# me433_hw2.net
KiCad netlist of a schematic drawn in EAGLE
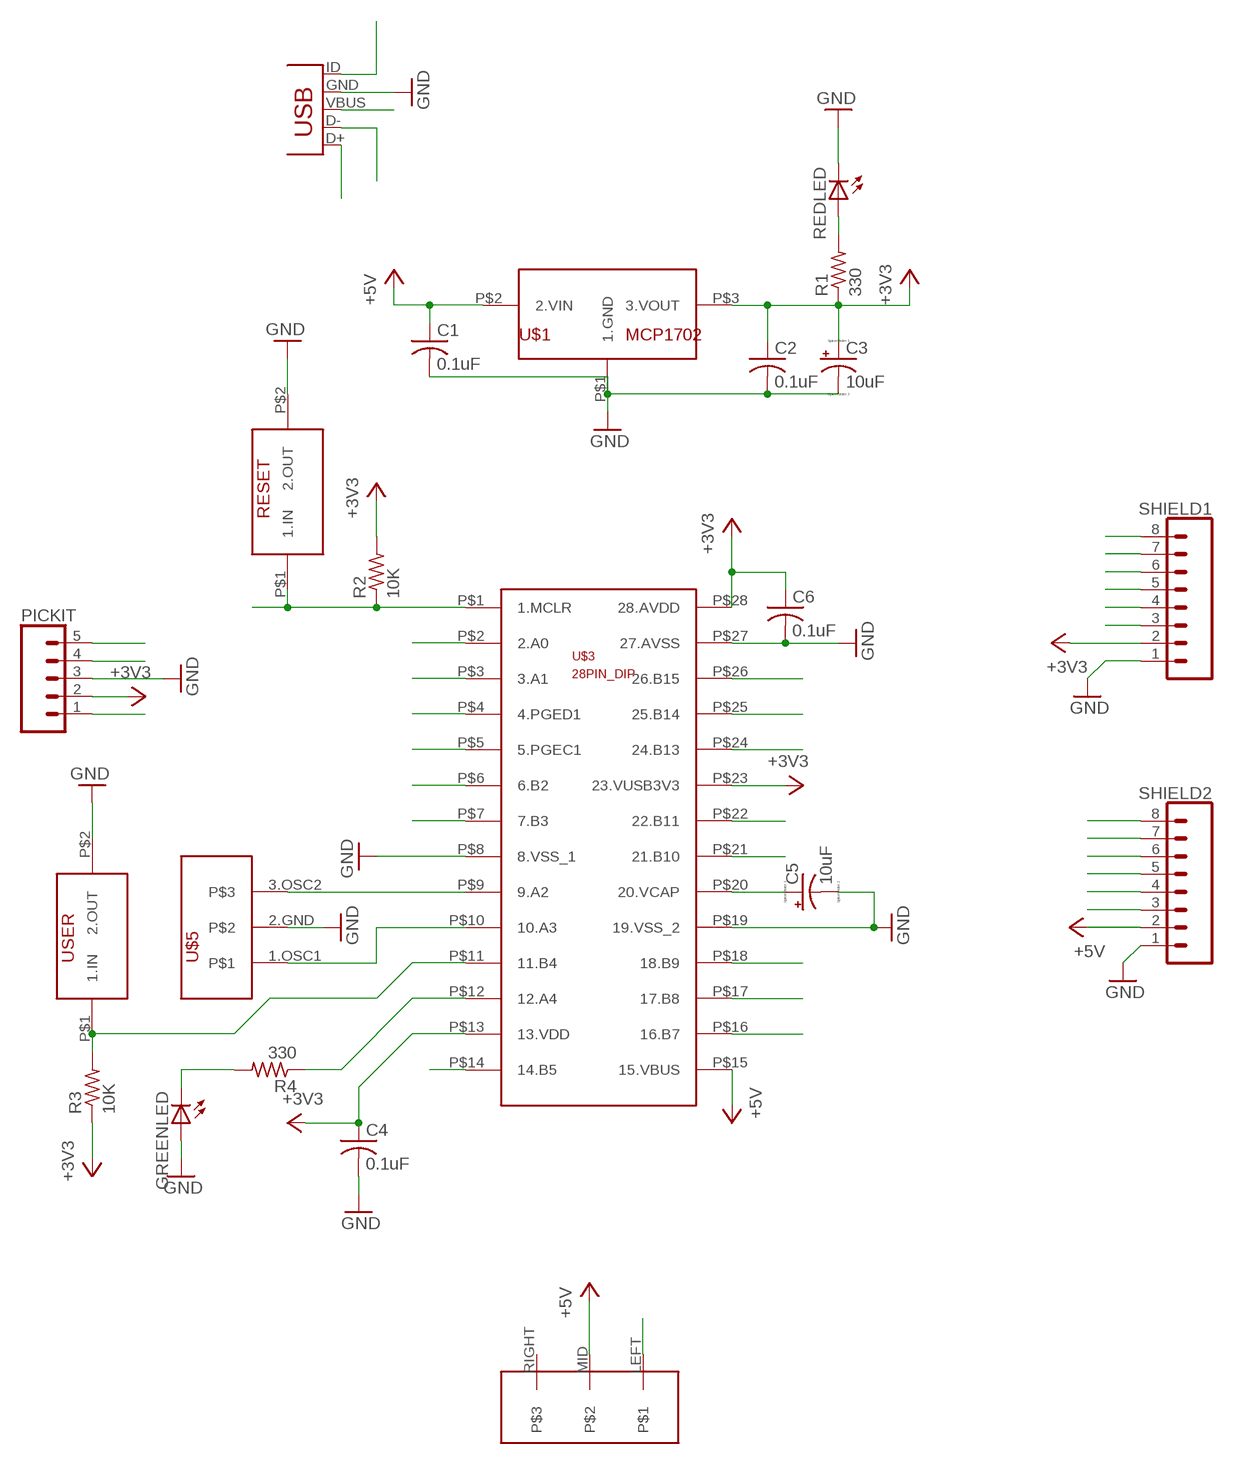
[diagram p0: schematic, sheet 1]

(export (version "E")
  (design (tool "Eeschema 10.0.6"))
  (components
    (comp (ref "C1")
      (value "0.1uF")
      (footprint "eagle-import:C025-030X050")
      (libsource (lib "eagle-import") (part "C-US025-030X050"))
    )
    (comp (ref "C2")
      (value "0.1uF")
      (footprint "eagle-import:C025-030X050")
      (libsource (lib "eagle-import") (part "C-US025-030X050"))
    )
    (comp (ref "C3")
      (value "10uF")
      (footprint "eagle-import:B45181B")
      (libsource (lib "eagle-import") (part "CPOL-USB45181B"))
    )
    (comp (ref "C4")
      (value "0.1uF")
      (footprint "eagle-import:C025-030X050")
      (libsource (lib "eagle-import") (part "C-US025-030X050"))
    )
    (comp (ref "C5")
      (value "10uF")
      (footprint "eagle-import:B45181B")
      (libsource (lib "eagle-import") (part "CPOL-USB45181B"))
    )
    (comp (ref "C6")
      (value "0.1uF")
      (footprint "eagle-import:C025-030X050")
      (libsource (lib "eagle-import") (part "C-US025-030X050"))
    )
    (comp (ref "GREENLED")
      (value "LED3MM")
      (footprint "eagle-import:LED3MM")
      (libsource (lib "eagle-import") (part "LED3MM"))
    )
    (comp (ref "PICKIT")
      (value "CONN_05")
      (footprint "eagle-import:1X05")
      (libsource (lib "eagle-import") (part "CONN_05"))
    )
    (comp (ref "R1")
      (value "330")
      (footprint "eagle-import:0207_10")
      (libsource (lib "eagle-import") (part "R-US_0207/10"))
    )
    (comp (ref "R2")
      (value "10K")
      (footprint "eagle-import:0207_10")
      (libsource (lib "eagle-import") (part "R-US_0207/10"))
    )
    (comp (ref "R3")
      (value "10K")
      (footprint "eagle-import:0207_10")
      (libsource (lib "eagle-import") (part "R-US_0207/10"))
    )
    (comp (ref "R4")
      (value "330")
      (footprint "eagle-import:0207_10")
      (libsource (lib "eagle-import") (part "R-US_0207/10"))
    )
    (comp (ref "REDLED")
      (value "LED3MM")
      (footprint "eagle-import:LED3MM")
      (libsource (lib "eagle-import") (part "LED3MM"))
    )
    (comp (ref "RESET")
      (value "PUSH_BUTTON")
      (footprint "eagle-import:PUSH_BUTTON")
      (libsource (lib "eagle-import") (part "PUSH_BUTTON"))
    )
    (comp (ref "SHIELD1")
      (value "CONN_08\"")
      (footprint "eagle-import:1X08")
      (libsource (lib "eagle-import") (part "CONN_08{dblquote}"))
    )
    (comp (ref "SHIELD2")
      (value "CONN_08\"")
      (footprint "eagle-import:1X08")
      (libsource (lib "eagle-import") (part "CONN_08{dblquote}"))
    )
    (comp (ref "U$1")
      (value "MCP1702")
      (footprint "eagle-import:MCP1702")
      (libsource (lib "eagle-import") (part "MCP1702"))
    )
    (comp (ref "U$2")
      (value "USBMINIB")
      (footprint "eagle-import:USB-MB-H")
      (libsource (lib "eagle-import") (part "USBMINIB"))
    )
    (comp (ref "U$3")
      (value "28PIN_DIP")
      (footprint "eagle-import:28PIN_DIP")
      (libsource (lib "eagle-import") (part "28PIN_DIP"))
    )
    (comp (ref "U$4")
      (value "SLIDE_SWITCH")
      (footprint "eagle-import:SLIDE_SWITCH")
      (libsource (lib "eagle-import") (part "SLIDE_SWITCH"))
    )
    (comp (ref "U$5")
      (value "RESONATOR")
      (footprint "eagle-import:RESONATOR")
      (libsource (lib "eagle-import") (part "RESONATOR"))
    )
    (comp (ref "USER")
      (value "PUSH_BUTTON")
      (footprint "eagle-import:PUSH_BUTTON")
      (libsource (lib "eagle-import") (part "PUSH_BUTTON"))
    )
  )
  (nets
    (net (code "1") (name "+3V3") (class "Default")
      (node (ref "C2") (pin "1") (pinfunction "1_1") (pintype "passive"))
      (node (ref "C3") (pin "+") (pinfunction "+_+") (pintype "passive"))
      (node (ref "C4") (pin "1") (pinfunction "1_1") (pintype "passive"))
      (node (ref "C6") (pin "1") (pinfunction "1_1") (pintype "passive"))
      (node (ref "PICKIT") (pin "2") (pinfunction "2_2") (pintype "passive"))
      (node (ref "R1") (pin "1") (pinfunction "1_1") (pintype "passive"))
      (node (ref "R2") (pin "2") (pinfunction "2_2") (pintype "passive"))
      (node (ref "R3") (pin "1") (pinfunction "1_1") (pintype "passive"))
      (node (ref "SHIELD1") (pin "2") (pinfunction "2_2") (pintype "passive"))
      (node (ref "U$1") (pin "P$3") (pinfunction "3.VOUT_P$3") (pintype "bidirectional"))
      (node (ref "U$3") (pin "P$13") (pinfunction "13.VDD_P$13") (pintype "bidirectional"))
      (node (ref "U$3") (pin "P$23") (pinfunction "23.VUSB3V3_P$23") (pintype "bidirectional"))
      (node (ref "U$3") (pin "P$28") (pinfunction "28.AVDD_P$28") (pintype "bidirectional"))
    )
    (net (code "2") (name "+5V") (class "Default")
      (node (ref "C1") (pin "1") (pinfunction "1_1") (pintype "passive"))
      (node (ref "SHIELD2") (pin "2") (pinfunction "2_2") (pintype "passive"))
      (node (ref "U$1") (pin "P$2") (pinfunction "2.VIN_P$2") (pintype "bidirectional"))
      (node (ref "U$3") (pin "P$15") (pinfunction "15.VBUS_P$15") (pintype "bidirectional"))
      (node (ref "U$4") (pin "MID") (pinfunction "P$2_MID") (pintype "bidirectional"))
    )
    (net (code "3") (name "/A0") (class "Default")
      (node (ref "SHIELD1") (pin "8") (pinfunction "8_8") (pintype "passive"))
      (node (ref "U$3") (pin "P$2") (pinfunction "2.A0_P$2") (pintype "bidirectional"))
    )
    (net (code "4") (name "/A1") (class "Default")
      (node (ref "SHIELD1") (pin "7") (pinfunction "7_7") (pintype "passive"))
      (node (ref "U$3") (pin "P$3") (pinfunction "3.A1_P$3") (pintype "bidirectional"))
    )
    (net (code "5") (name "/A4") (class "Default")
      (node (ref "R4") (pin "1") (pinfunction "1_1") (pintype "passive"))
      (node (ref "SHIELD1") (pin "3") (pinfunction "3_3") (pintype "passive"))
      (node (ref "U$3") (pin "P$12") (pinfunction "12.A4_P$12") (pintype "bidirectional"))
    )
    (net (code "6") (name "/B2") (class "Default")
      (node (ref "SHIELD1") (pin "6") (pinfunction "6_6") (pintype "passive"))
      (node (ref "U$3") (pin "P$6") (pinfunction "6.B2_P$6") (pintype "bidirectional"))
    )
    (net (code "7") (name "/B3") (class "Default")
      (node (ref "SHIELD1") (pin "5") (pinfunction "5_5") (pintype "passive"))
      (node (ref "U$3") (pin "P$7") (pinfunction "7.B3_P$7") (pintype "bidirectional"))
    )
    (net (code "8") (name "/B4") (class "Default")
      (node (ref "R3") (pin "2") (pinfunction "2_2") (pintype "passive"))
      (node (ref "SHIELD1") (pin "4") (pinfunction "4_4") (pintype "passive"))
      (node (ref "U$3") (pin "P$11") (pinfunction "11.B4_P$11") (pintype "bidirectional"))
      (node (ref "USER") (pin "P$1") (pinfunction "1.IN_P$1") (pintype "bidirectional"))
    )
    (net (code "9") (name "/B7") (class "Default")
      (node (ref "SHIELD2") (pin "3") (pinfunction "3_3") (pintype "passive"))
      (node (ref "U$3") (pin "P$16") (pinfunction "16.B7_P$16") (pintype "bidirectional"))
    )
    (net (code "10") (name "/B8") (class "Default")
      (node (ref "SHIELD2") (pin "4") (pinfunction "4_4") (pintype "passive"))
      (node (ref "U$3") (pin "P$17") (pinfunction "17.B8_P$17") (pintype "bidirectional"))
    )
    (net (code "11") (name "/B9") (class "Default")
      (node (ref "SHIELD2") (pin "5") (pinfunction "5_5") (pintype "passive"))
      (node (ref "U$3") (pin "P$18") (pinfunction "18.B9_P$18") (pintype "bidirectional"))
    )
    (net (code "12") (name "/B13") (class "Default")
      (node (ref "SHIELD2") (pin "6") (pinfunction "6_6") (pintype "passive"))
      (node (ref "U$3") (pin "P$24") (pinfunction "24.B13_P$24") (pintype "bidirectional"))
    )
    (net (code "13") (name "/B14") (class "Default")
      (node (ref "SHIELD2") (pin "7") (pinfunction "7_7") (pintype "passive"))
      (node (ref "U$3") (pin "P$25") (pinfunction "25.B14_P$25") (pintype "bidirectional"))
    )
    (net (code "14") (name "/B15") (class "Default")
      (node (ref "SHIELD2") (pin "8") (pinfunction "8_8") (pintype "passive"))
      (node (ref "U$3") (pin "P$26") (pinfunction "26.B15_P$26") (pintype "bidirectional"))
    )
    (net (code "15") (name "/D+") (class "Default")
      (node (ref "U$2") (pin "D+") (pinfunction "D+_D+") (pintype "bidirectional"))
      (node (ref "U$3") (pin "P$21") (pinfunction "21.B10_P$21") (pintype "bidirectional"))
    )
    (net (code "16") (name "/D-") (class "Default")
      (node (ref "U$2") (pin "D-") (pinfunction "D-_D-") (pintype "bidirectional"))
      (node (ref "U$3") (pin "P$22") (pinfunction "22.B11_P$22") (pintype "bidirectional"))
    )
    (net (code "17") (name "/MCLR") (class "Default")
      (node (ref "PICKIT") (pin "1") (pinfunction "1_1") (pintype "passive"))
      (node (ref "R2") (pin "1") (pinfunction "1_1") (pintype "passive"))
      (node (ref "RESET") (pin "P$1") (pinfunction "1.IN_P$1") (pintype "bidirectional"))
      (node (ref "U$3") (pin "P$1") (pinfunction "1.MCLR_P$1") (pintype "bidirectional"))
    )
    (net (code "18") (name "/PGC1") (class "Default")
      (node (ref "PICKIT") (pin "5") (pinfunction "5_5") (pintype "passive"))
      (node (ref "U$3") (pin "P$5") (pinfunction "5.PGEC1_P$5") (pintype "bidirectional"))
    )
    (net (code "19") (name "/PGD1") (class "Default")
      (node (ref "PICKIT") (pin "4") (pinfunction "4_4") (pintype "passive"))
      (node (ref "U$3") (pin "P$4") (pinfunction "4.PGED1_P$4") (pintype "bidirectional"))
    )
    (net (code "20") (name "/SLIDESWITCH") (class "Default")
      (node (ref "U$2") (pin "VBUS") (pinfunction "VBUS_VBUS") (pintype "bidirectional"))
      (node (ref "U$4") (pin "LEFT") (pinfunction "P$1_LEFT") (pintype "bidirectional"))
    )
    (net (code "21") (name "/USBID") (class "Default")
      (node (ref "U$2") (pin "ID") (pinfunction "USBID_ID") (pintype "bidirectional"))
      (node (ref "U$3") (pin "P$14") (pinfunction "14.B5_P$14") (pintype "bidirectional"))
    )
    (net (code "22") (name "GND") (class "Default")
      (node (ref "C1") (pin "2") (pinfunction "2_2") (pintype "passive"))
      (node (ref "C2") (pin "2") (pinfunction "2_2") (pintype "passive"))
      (node (ref "C3") (pin "-") (pinfunction "-_-") (pintype "passive"))
      (node (ref "C4") (pin "2") (pinfunction "2_2") (pintype "passive"))
      (node (ref "C5") (pin "-") (pinfunction "-_-") (pintype "passive"))
      (node (ref "C6") (pin "2") (pinfunction "2_2") (pintype "passive"))
      (node (ref "GREENLED") (pin "A") (pinfunction "A_A") (pintype "passive"))
      (node (ref "PICKIT") (pin "3") (pinfunction "3_3") (pintype "passive"))
      (node (ref "REDLED") (pin "K") (pinfunction "C_K") (pintype "passive"))
      (node (ref "RESET") (pin "P$2") (pinfunction "2.OUT_P$2") (pintype "bidirectional"))
      (node (ref "SHIELD1") (pin "1") (pinfunction "1_1") (pintype "passive"))
      (node (ref "SHIELD2") (pin "1") (pinfunction "1_1") (pintype "passive"))
      (node (ref "U$1") (pin "P$1") (pinfunction "1.GND_P$1") (pintype "bidirectional"))
      (node (ref "U$2") (pin "GND") (pinfunction "GND_GND") (pintype "bidirectional"))
      (node (ref "U$3") (pin "P$19") (pinfunction "19.VSS_2_P$19") (pintype "bidirectional"))
      (node (ref "U$3") (pin "P$27") (pinfunction "27.AVSS_P$27") (pintype "bidirectional"))
      (node (ref "U$3") (pin "P$8") (pinfunction "8.VSS_1_P$8") (pintype "bidirectional"))
      (node (ref "U$5") (pin "2.GND") (pinfunction "P$2_2.GND") (pintype "bidirectional"))
      (node (ref "USER") (pin "P$2") (pinfunction "2.OUT_P$2") (pintype "bidirectional"))
    )
    (net (code "23") (name "Net-(GREENLED-C)") (class "Default")
      (node (ref "GREENLED") (pin "K") (pinfunction "C_K") (pintype "passive"))
      (node (ref "R4") (pin "2") (pinfunction "2_2") (pintype "passive"))
    )
    (net (code "24") (name "Net-(R1-Pad2)") (class "Default")
      (node (ref "R1") (pin "2") (pinfunction "2_2") (pintype "passive"))
      (node (ref "REDLED") (pin "A") (pinfunction "A_A") (pintype "passive"))
    )
    (net (code "25") (name "Net-(U$3-9.A2)") (class "Default")
      (node (ref "U$3") (pin "P$9") (pinfunction "9.A2_P$9") (pintype "bidirectional"))
      (node (ref "U$5") (pin "3.OSC2") (pinfunction "P$3_3.OSC2") (pintype "bidirectional"))
    )
    (net (code "26") (name "Net-(U$3-10.A3)") (class "Default")
      (node (ref "U$3") (pin "P$10") (pinfunction "10.A3_P$10") (pintype "bidirectional"))
      (node (ref "U$5") (pin "1.OSC1") (pinfunction "P$1_1.OSC1") (pintype "bidirectional"))
    )
    (net (code "27") (name "Net-(U$3-20.VCAP)") (class "Default")
      (node (ref "C5") (pin "+") (pinfunction "+_+") (pintype "passive"))
      (node (ref "U$3") (pin "P$20") (pinfunction "20.VCAP_P$20") (pintype "bidirectional"))
    )
    (net (code "28") (name "unconnected-(U$4-P$3-PadRIGHT)") (class "Default")
      (node (ref "U$4") (pin "RIGHT") (pinfunction "P$3_RIGHT") (pintype "bidirectional"))
    )
  )
)
